# EPS_MPPT_X_Boost-Converter.net
KiCad netlist of a schematic drawn in Altium Designer
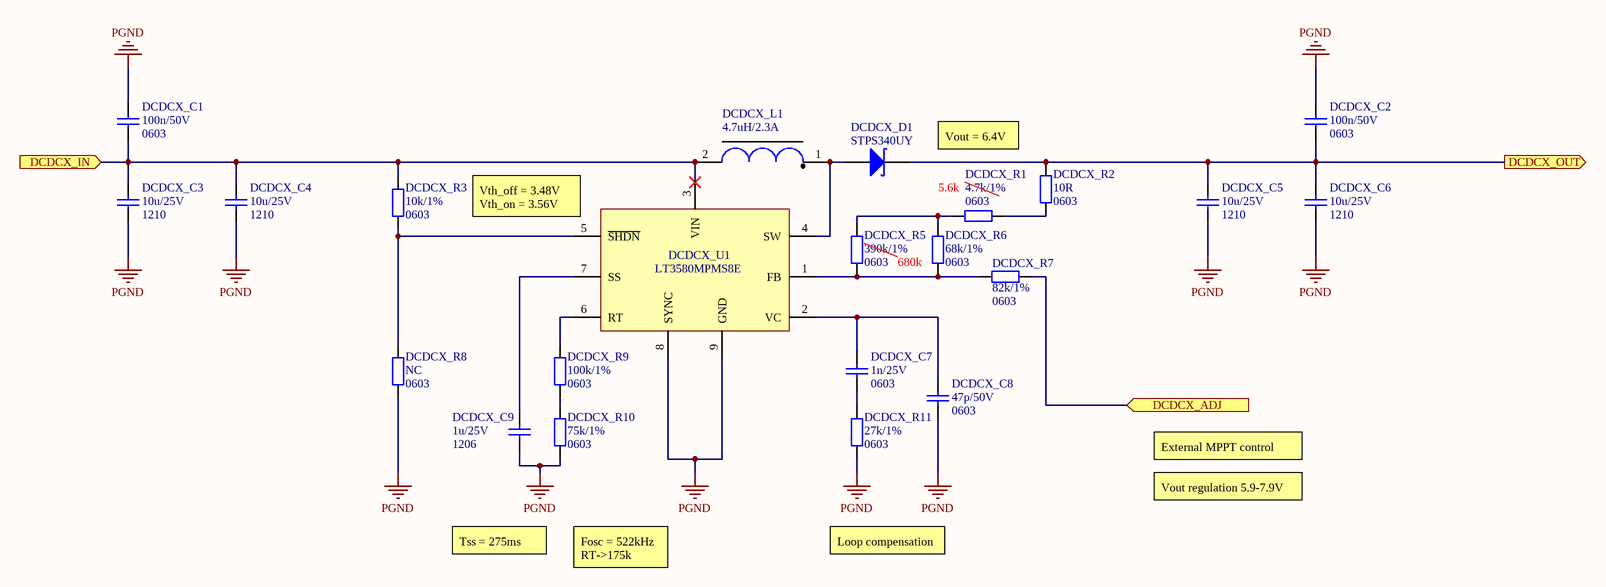
[diagram p0: EPS_MPPT_X_Boost-Converter.SchDoc]

(export (version "E")
  (design (tool "Eeschema 10.0.6"))
  (components
    (comp (ref "DCDCX_C1")
      (value "100n/50V")
      (footprint "SMD_Capacitor_0603")
      (description "Ceramic Cap Kemet COTS 100n/50V X7R 0603")
      (fields
        (field (name "MANUFACTURER") "Kemet")
        (field (name "MANUFACTURERPARTNUMBER") "C0603T104K5RALTU")
        (field (name "PACKAGE") "0603")
      )
      (libsource (lib "capacitors") (part "Cer_C0603T104K5RALTU"))
    )
    (comp (ref "DCDCX_C2")
      (value "100n/50V")
      (footprint "SMD_Capacitor_0603")
      (description "Ceramic Cap Kemet COTS 100n/50V X7R 0603")
      (fields
        (field (name "MANUFACTURER") "Kemet")
        (field (name "MANUFACTURERPARTNUMBER") "C0603T104K5RALTU")
        (field (name "PACKAGE") "0603")
      )
      (libsource (lib "capacitors") (part "Cer_C0603T104K5RALTU"))
    )
    (comp (ref "DCDCX_C3")
      (value "10u/25V")
      (footprint "SMD_Capacitor_1210")
      (description "Ceramic Cap Murata Automotive 10u/25V X7R 1210")
      (fields
        (field (name "MANUFACTURER") "Murata")
        (field (name "MANUFACTURERPARTNUMBER") "GCJ32ER71E106KA12L")
        (field (name "PACKAGE") "1210")
      )
      (libsource (lib "capacitors") (part "Cer_GCJ32ER71E106KA12L"))
    )
    (comp (ref "DCDCX_C4")
      (value "10u/25V")
      (footprint "SMD_Capacitor_1210")
      (description "Ceramic Cap Murata Automotive 10u/25V X7R 1210")
      (fields
        (field (name "MANUFACTURER") "Murata")
        (field (name "MANUFACTURERPARTNUMBER") "GCJ32ER71E106KA12L")
        (field (name "PACKAGE") "1210")
      )
      (libsource (lib "capacitors") (part "Cer_GCJ32ER71E106KA12L"))
    )
    (comp (ref "DCDCX_C5")
      (value "10u/25V")
      (footprint "SMD_Capacitor_1210")
      (description "Ceramic Cap Murata Automotive 10u/25V X7R 1210")
      (fields
        (field (name "MANUFACTURER") "Murata")
        (field (name "MANUFACTURERPARTNUMBER") "GCJ32ER71E106KA12L")
        (field (name "PACKAGE") "1210")
      )
      (libsource (lib "capacitors") (part "Cer_GCJ32ER71E106KA12L"))
    )
    (comp (ref "DCDCX_C6")
      (value "10u/25V")
      (footprint "SMD_Capacitor_1210")
      (description "Ceramic Cap Murata Automotive 10u/25V X7R 1210")
      (fields
        (field (name "MANUFACTURER") "Murata")
        (field (name "MANUFACTURERPARTNUMBER") "GCJ32ER71E106KA12L")
        (field (name "PACKAGE") "1210")
      )
      (libsource (lib "capacitors") (part "Cer_GCJ32ER71E106KA12L"))
    )
    (comp (ref "DCDCX_C7")
      (value "1n/25V")
      (footprint "SMD_Capacitor_0603")
      (description "Cap")
      (fields (field (name "PACKAGE") "0603"))
      (libsource (lib "capacitors") (part "Cap"))
    )
    (comp (ref "DCDCX_C8")
      (value "47p/50V")
      (footprint "SMD_Capacitor_0603")
      (description "Cap")
      (fields (field (name "PACKAGE") "0603"))
      (libsource (lib "capacitors") (part "Cap"))
    )
    (comp (ref "DCDCX_C9")
      (value "1u/25V")
      (footprint "SMD_Capacitor_1206")
      (description "Ceramic Cap Kemet COTS 1u/25V X7R 1206")
      (fields
        (field (name "MANUFACTURERPARTNUMBER") "C1206T105K3RALTU")
        (field (name "MANUFACTURER") "Kemet")
        (field (name "PACKAGE") "1206")
      )
      (libsource (lib "capacitors") (part "Cer_C1206T105K3RALTU"))
    )
    (comp (ref "DCDCX_D1")
      (value "STPS340UY")
      (footprint "DO-214AA")
      (description "3A/40V Power Schottky Rectifier.")
      (fields (field (name "MANUFACTURER") "STMicroelectronics"))
      (libsource (lib "diodes") (part "STPS340x"))
    )
    (comp (ref "DCDCX_L1")
      (value "4.7uH/2.3A")
      (footprint "Coilcraft_MSS6132")
      (description "Coilcraft MSS6132 Inductor, L=4.7uH, Irise20deg=2.3A, ESR=43mR, SRF=65MHz.")
      (fields
        (field (name "MANUFACTURER") "Coilcraft")
        (field (name "MANUFACTURERPARTNUMBER") "MSS6132-472MLx")
      )
      (libsource (lib "inductors") (part "MSS6132-472MLx"))
    )
    (comp (ref "DCDCX_R1")
      (value "4.7k/1%")
      (footprint "SMD_Resistor_0603")
      (fields (field (name "PACKAGE") "0603"))
      (libsource (lib "resistors") (part "Res"))
    )
    (comp (ref "DCDCX_R2")
      (value "10R")
      (footprint "SMD_Resistor_0603")
      (fields (field (name "PACKAGE") "0603"))
      (libsource (lib "") (part "Res_2"))
    )
    (comp (ref "DCDCX_R3")
      (value "10k/1%")
      (footprint "SMD_Resistor_0603")
      (fields (field (name "PACKAGE") "0603"))
      (libsource (lib "") (part "Res_1"))
    )
    (comp (ref "DCDCX_R5")
      (value "390k/1%")
      (footprint "SMD_Resistor_0603")
      (fields (field (name "PACKAGE") "0603"))
      (libsource (lib "") (part "Res_1"))
    )
    (comp (ref "DCDCX_R6")
      (value "68k/1%")
      (footprint "SMD_Resistor_0603")
      (fields (field (name "PACKAGE") "0603"))
      (libsource (lib "") (part "Res_1"))
    )
    (comp (ref "DCDCX_R7")
      (value "82k/1%")
      (footprint "SMD_Resistor_0603")
      (fields (field (name "PACKAGE") "0603"))
      (libsource (lib "resistors") (part "Res"))
    )
    (comp (ref "DCDCX_R8")
      (value "NC")
      (footprint "SMD_Resistor_0603")
      (fields (field (name "PACKAGE") "0603"))
      (libsource (lib "") (part "Res_1"))
    )
    (comp (ref "DCDCX_R9")
      (value "100k/1%")
      (footprint "SMD_Resistor_0603")
      (fields (field (name "PACKAGE") "0603"))
      (libsource (lib "") (part "Res_1"))
    )
    (comp (ref "DCDCX_R10")
      (value "75k/1%")
      (footprint "SMD_Resistor_0603")
      (fields (field (name "PACKAGE") "0603"))
      (libsource (lib "") (part "Res_1"))
    )
    (comp (ref "DCDCX_R11")
      (value "27k/1%")
      (footprint "SMD_Resistor_0603")
      (fields (field (name "PACKAGE") "0603"))
      (libsource (lib "") (part "Res_1"))
    )
    (comp (ref "DCDCX_U1")
      (value "~")
      (footprint "LT-MS8E-8-1880X1680TP_N")
      (description "Boost Conv 2A, Soft-Start, Synchro")
      (fields
        (field (name "MANUFACTURER") "Linear Technology")
        (field (name "MANUFACTURERPARTNUMBER") "LT3580MPMS8E")
      )
      (libsource (lib "microcircuits") (part "LT3580MPMS8E"))
    )
  )
  (nets
    (net (code "1") (name "/DCDCX_ADJ") (class "Default")
      (node (ref "DCDCX_R7") (pin "2") (pinfunction "2_2") (pintype "passive"))
    )
    (net (code "2") (name "/DCDCX_IN") (class "Default")
      (node (ref "DCDCX_C1") (pin "2") (pinfunction "2_2") (pintype "passive"))
      (node (ref "DCDCX_C3") (pin "1") (pinfunction "1_1") (pintype "passive"))
      (node (ref "DCDCX_C4") (pin "1") (pinfunction "1_1") (pintype "passive"))
      (node (ref "DCDCX_L1") (pin "2") (pinfunction "2_2") (pintype "passive"))
      (node (ref "DCDCX_R3") (pin "1") (pinfunction "1_1") (pintype "passive"))
      (node (ref "DCDCX_U1") (pin "3") (pinfunction "VIN_3") (pintype "power_in"))
    )
    (net (code "3") (name "/DCDCX_OUT") (class "Default")
      (node (ref "DCDCX_C2") (pin "2") (pinfunction "2_2") (pintype "passive"))
      (node (ref "DCDCX_C5") (pin "1") (pinfunction "1_1") (pintype "passive"))
      (node (ref "DCDCX_C6") (pin "1") (pinfunction "1_1") (pintype "passive"))
      (node (ref "DCDCX_D1") (pin "K") (pinfunction "K_K") (pintype "passive"))
      (node (ref "DCDCX_R2") (pin "2") (pinfunction "2_2") (pintype "passive"))
    )
    (net (code "4") (name "Net-(DCDCX_C7-Pad2)") (class "Default")
      (node (ref "DCDCX_C7") (pin "2") (pinfunction "2_2") (pintype "passive"))
      (node (ref "DCDCX_R11") (pin "1") (pinfunction "1_1") (pintype "passive"))
    )
    (net (code "5") (name "Net-(DCDCX_R1-Pad1)") (class "Default")
      (node (ref "DCDCX_R1") (pin "1") (pinfunction "1_1") (pintype "passive"))
      (node (ref "DCDCX_R5") (pin "1") (pinfunction "1_1") (pintype "passive"))
      (node (ref "DCDCX_R6") (pin "1") (pinfunction "1_1") (pintype "passive"))
    )
    (net (code "6") (name "Net-(DCDCX_R1-Pad2)") (class "Default")
      (node (ref "DCDCX_R1") (pin "2") (pinfunction "2_2") (pintype "passive"))
      (node (ref "DCDCX_R2") (pin "1") (pinfunction "1_1") (pintype "passive"))
    )
    (net (code "7") (name "Net-(DCDCX_R10-Pad1)") (class "Default")
      (node (ref "DCDCX_R10") (pin "1") (pinfunction "1_1") (pintype "passive"))
      (node (ref "DCDCX_R9") (pin "2") (pinfunction "2_2") (pintype "passive"))
    )
    (net (code "8") (name "Net-(DCDCX_U1-FB)") (class "Default")
      (node (ref "DCDCX_R5") (pin "2") (pinfunction "2_2") (pintype "passive"))
      (node (ref "DCDCX_R6") (pin "2") (pinfunction "2_2") (pintype "passive"))
      (node (ref "DCDCX_R7") (pin "1") (pinfunction "1_1") (pintype "passive"))
      (node (ref "DCDCX_U1") (pin "1") (pinfunction "FB_1") (pintype "passive"))
    )
    (net (code "9") (name "Net-(DCDCX_U1-RT)") (class "Default")
      (node (ref "DCDCX_R9") (pin "1") (pinfunction "1_1") (pintype "passive"))
      (node (ref "DCDCX_U1") (pin "6") (pinfunction "RT_6") (pintype "passive"))
    )
    (net (code "10") (name "Net-(DCDCX_U1-SS)") (class "Default")
      (node (ref "DCDCX_C9") (pin "1") (pinfunction "1_1") (pintype "passive"))
      (node (ref "DCDCX_U1") (pin "7") (pinfunction "SS_7") (pintype "passive"))
    )
    (net (code "11") (name "Net-(DCDCX_U1-SW)") (class "Default")
      (node (ref "DCDCX_D1") (pin "A") (pinfunction "A_A") (pintype "passive"))
      (node (ref "DCDCX_L1") (pin "1") (pinfunction "1_1") (pintype "passive"))
      (node (ref "DCDCX_U1") (pin "4") (pinfunction "SW_4") (pintype "passive"))
    )
    (net (code "12") (name "Net-(DCDCX_U1-VC)") (class "Default")
      (node (ref "DCDCX_C7") (pin "1") (pinfunction "1_1") (pintype "passive"))
      (node (ref "DCDCX_C8") (pin "1") (pinfunction "1_1") (pintype "passive"))
      (node (ref "DCDCX_U1") (pin "2") (pinfunction "VC_2") (pintype "passive"))
    )
    (net (code "13") (name "Net-(DCDCX_U1-~{SHDN})") (class "Default")
      (node (ref "DCDCX_R3") (pin "2") (pinfunction "2_2") (pintype "passive"))
      (node (ref "DCDCX_R8") (pin "1") (pinfunction "1_1") (pintype "passive"))
      (node (ref "DCDCX_U1") (pin "5") (pinfunction "~{SHDN}_5") (pintype "passive"))
    )
    (net (code "14") (name "PGND") (class "Default")
      (node (ref "DCDCX_C1") (pin "1") (pinfunction "1_1") (pintype "passive"))
      (node (ref "DCDCX_C2") (pin "1") (pinfunction "1_1") (pintype "passive"))
      (node (ref "DCDCX_C3") (pin "2") (pinfunction "2_2") (pintype "passive"))
      (node (ref "DCDCX_C4") (pin "2") (pinfunction "2_2") (pintype "passive"))
      (node (ref "DCDCX_C5") (pin "2") (pinfunction "2_2") (pintype "passive"))
      (node (ref "DCDCX_C6") (pin "2") (pinfunction "2_2") (pintype "passive"))
      (node (ref "DCDCX_C8") (pin "2") (pinfunction "2_2") (pintype "passive"))
      (node (ref "DCDCX_C9") (pin "2") (pinfunction "2_2") (pintype "passive"))
      (node (ref "DCDCX_R10") (pin "2") (pinfunction "2_2") (pintype "passive"))
      (node (ref "DCDCX_R11") (pin "2") (pinfunction "2_2") (pintype "passive"))
      (node (ref "DCDCX_R8") (pin "2") (pinfunction "2_2") (pintype "passive"))
      (node (ref "DCDCX_U1") (pin "8") (pinfunction "SYNC_8") (pintype "passive"))
      (node (ref "DCDCX_U1") (pin "9") (pinfunction "GND_9") (pintype "passive"))
    )
  )
)
